# Aux_Power_Board.net
KiCad netlist of a schematic drawn in EAGLE
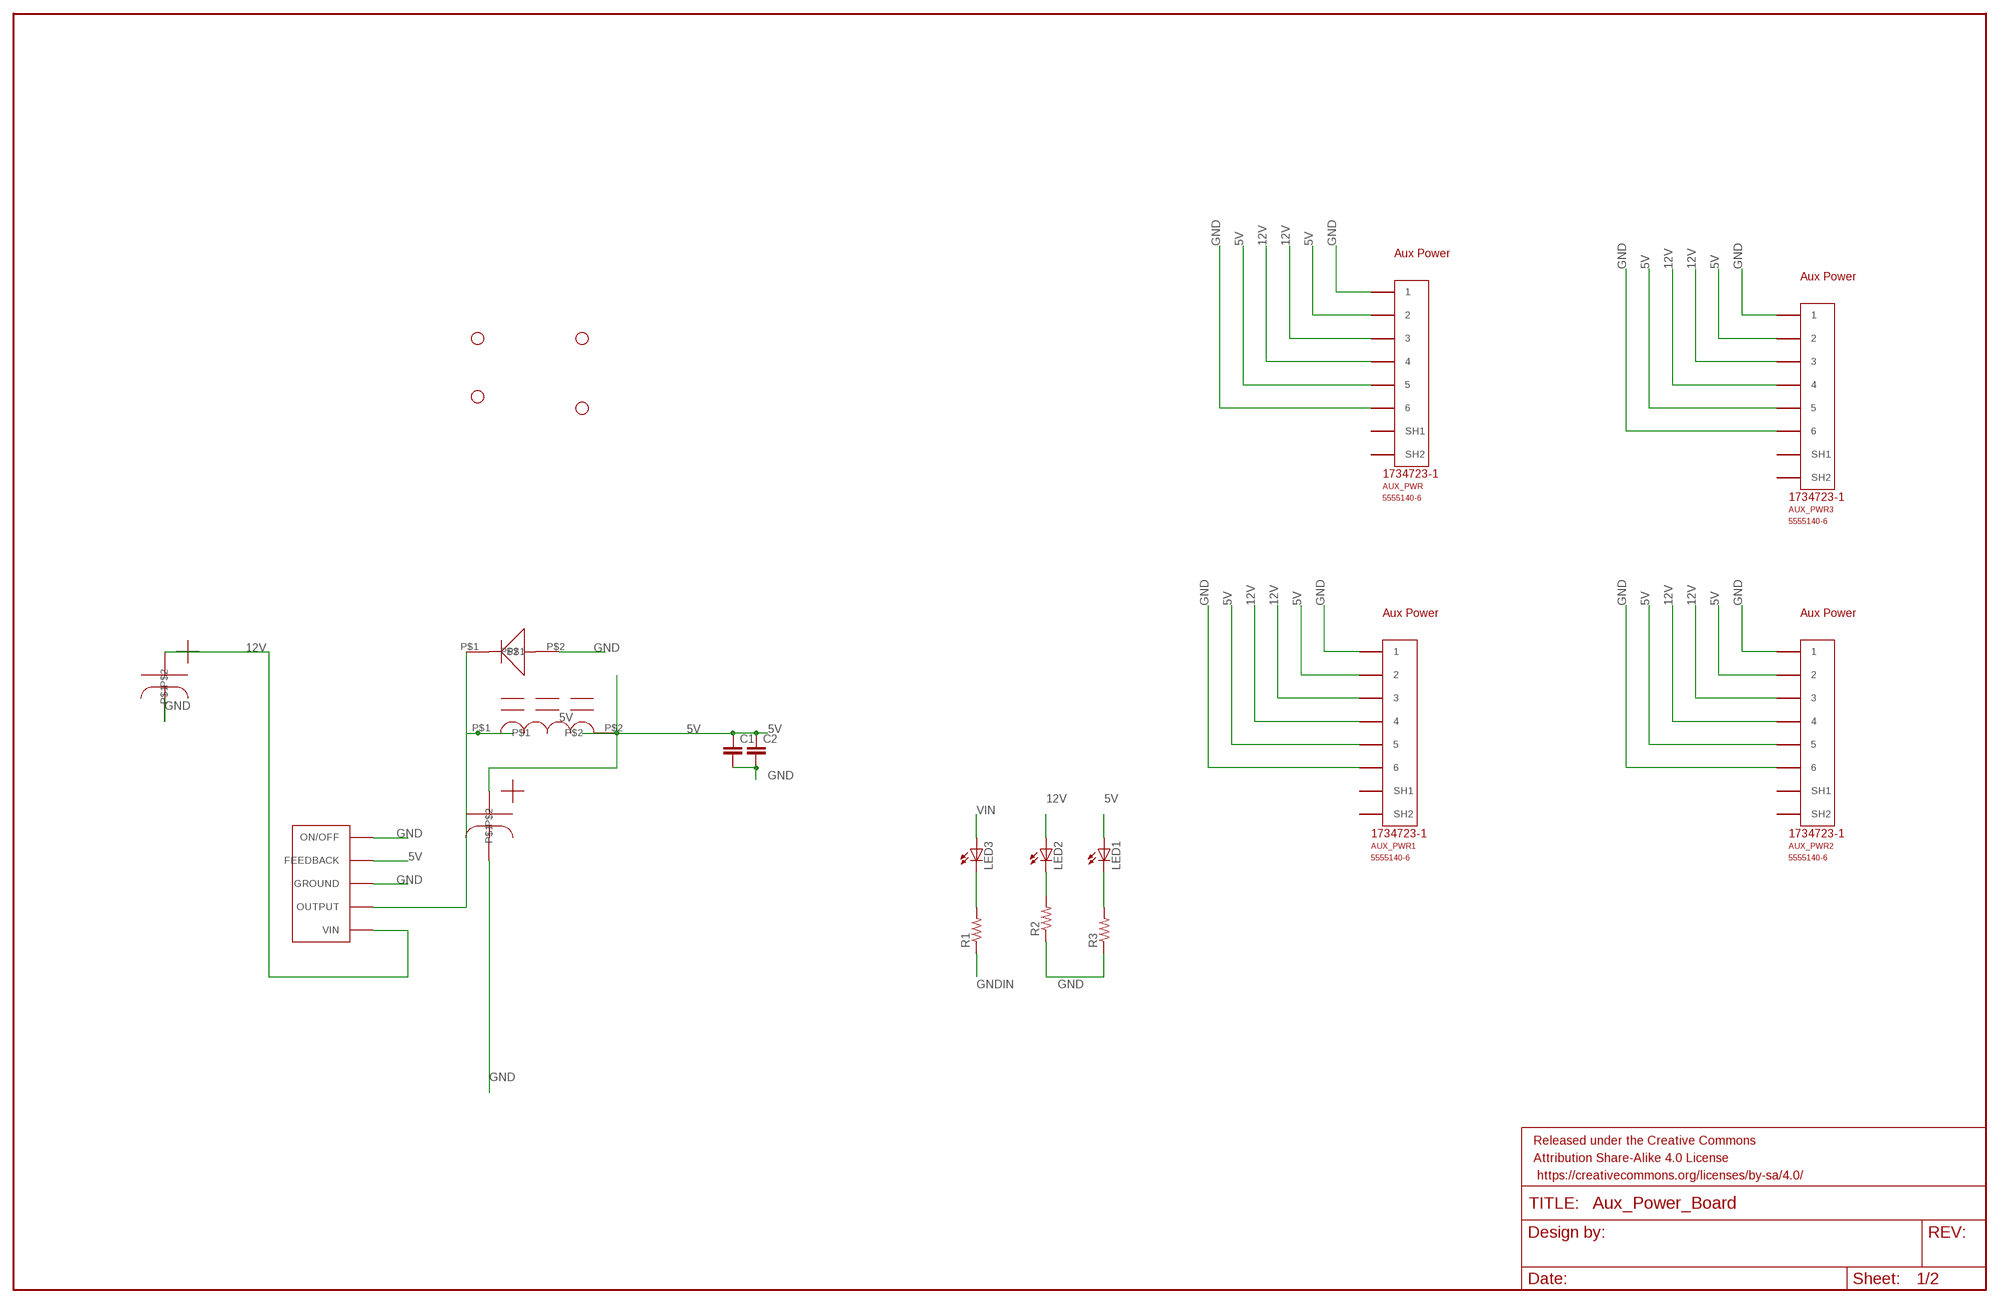
[diagram p0: schematic, sheet 1]
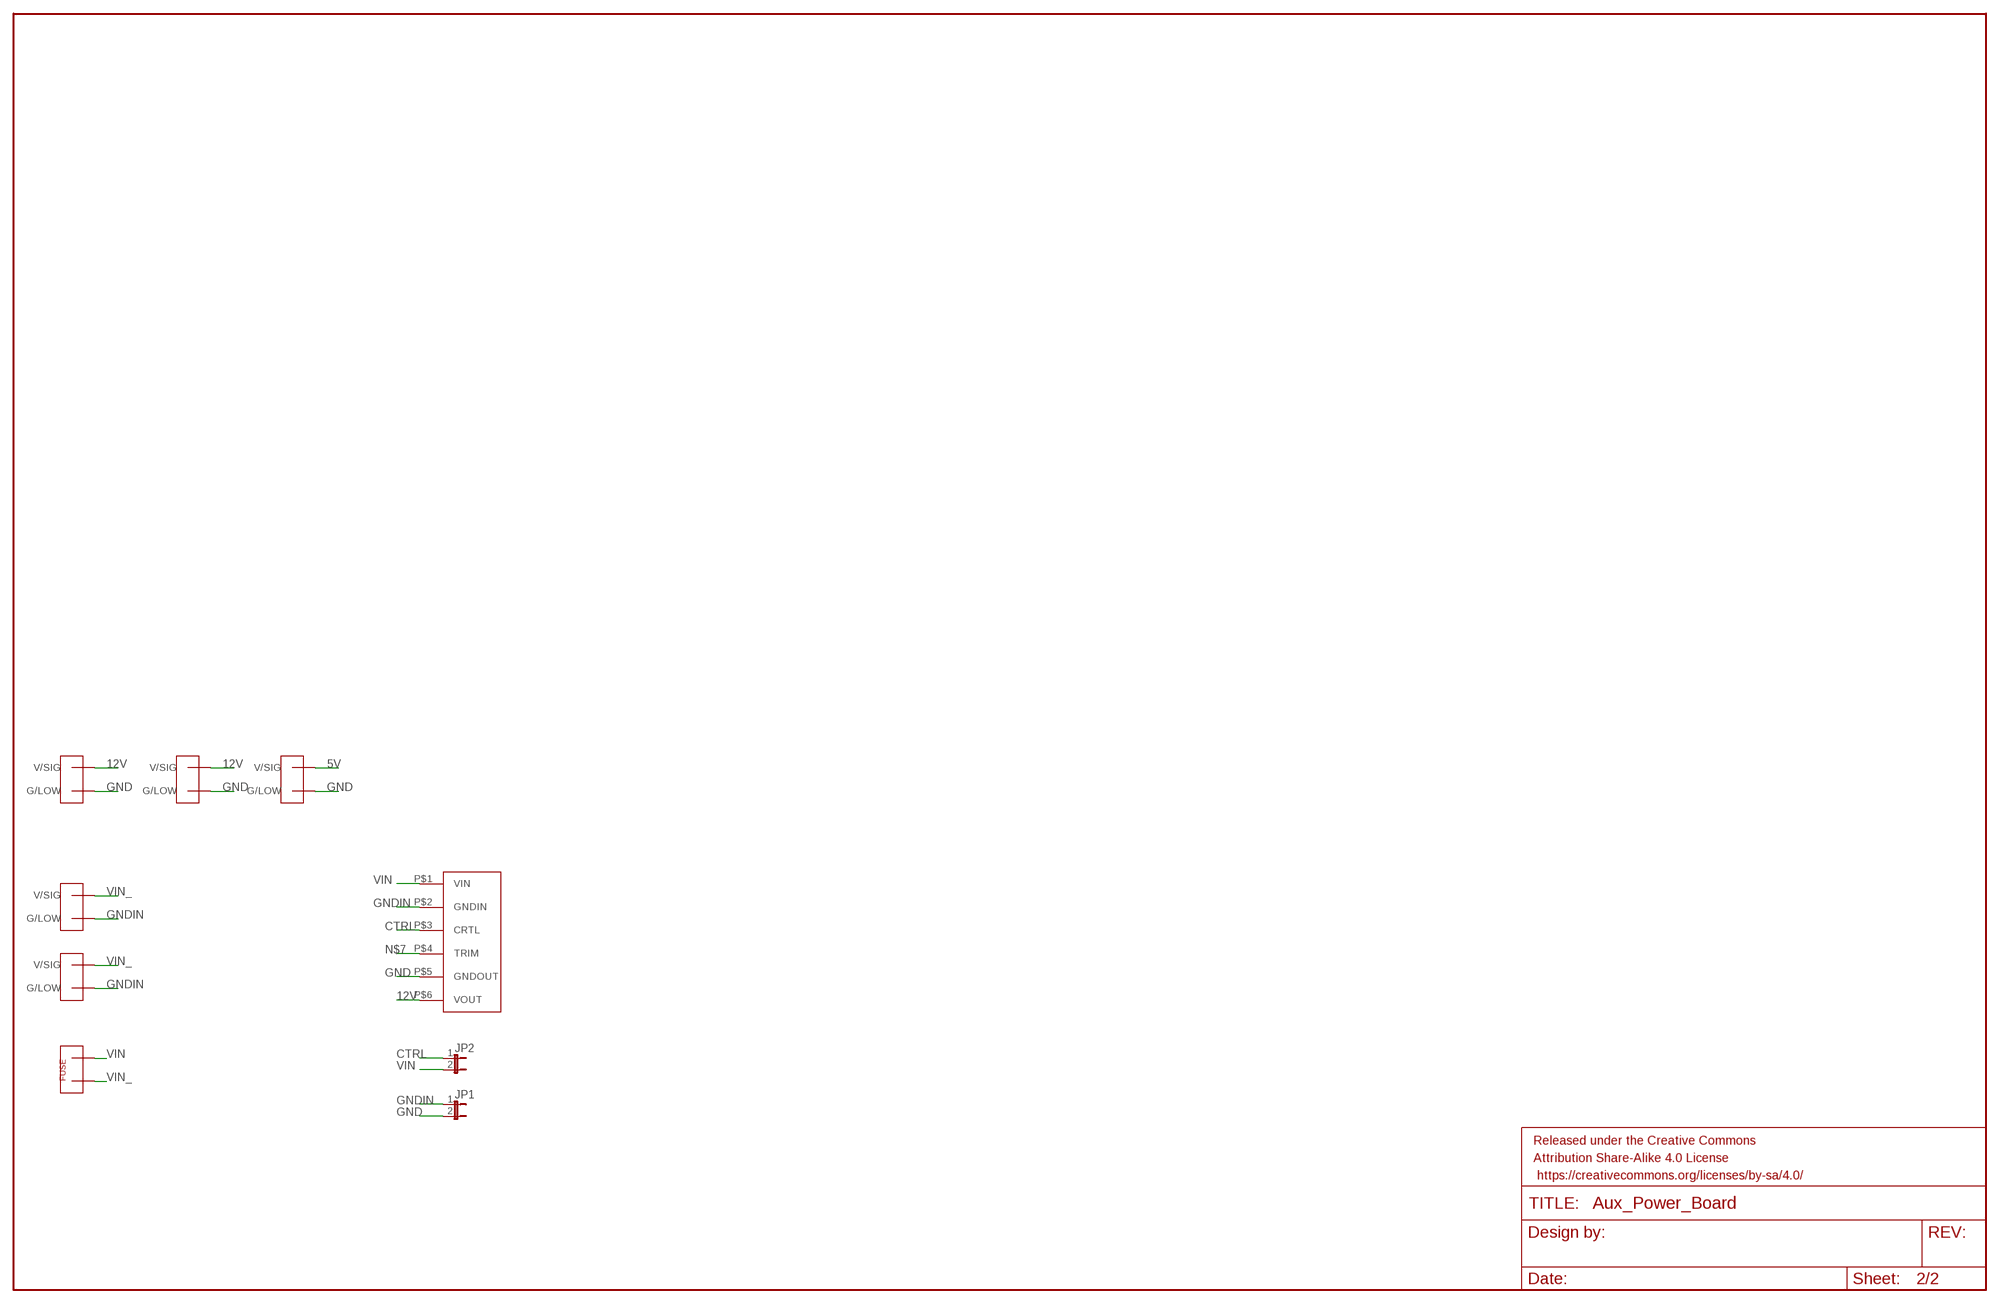
[diagram p1: schematic, sheet 2]

(export (version "E")
  (design (tool "Eeschema 10.0.6"))
  (components
    (comp (ref "FRAME2")
      (value "FRAME-LEDGER")
      (footprint "eagle-import:CREATIVE_COMMONS")
      (libsource (lib "eagle-import") (part "FRAME-LEDGER"))
    )
    (comp (ref "JP1")
      (value "JP1E")
      (footprint "eagle-import:JP1")
      (libsource (lib "eagle-import") (part "JP1E"))
    )
    (comp (ref "JP2")
      (value "JP1E")
      (footprint "eagle-import:JP1")
      (libsource (lib "eagle-import") (part "JP1E"))
    )
    (comp (ref "U$1")
      (value "TE770966")
      (footprint "eagle-import:2X1-MATE-N-LOCK")
      (libsource (lib "eagle-import") (part "TE770966"))
    )
    (comp (ref "U$2")
      (value "TE770966")
      (footprint "eagle-import:2X1-MATE-N-LOCK")
      (libsource (lib "eagle-import") (part "TE770966"))
    )
    (comp (ref "U$3")
      (value "TE770966")
      (footprint "eagle-import:2X1-MATE-N-LOCK")
      (libsource (lib "eagle-import") (part "TE770966"))
    )
    (comp (ref "U$12")
      (value "RPA60-2412SFW_P")
      (footprint "eagle-import:RPA60-2412SFW_P")
      (libsource (lib "eagle-import") (part "RPA60-2412SFW_P"))
    )
    (comp (ref "U$13")
      (value "FUSEMINI-BLADE")
      (footprint "eagle-import:MINI-BLADE-FUSE")
      (libsource (lib "eagle-import") (part "FUSEMINI-BLADE"))
    )
    (comp (ref "U$14")
      (value "TE770966")
      (footprint "eagle-import:2X1-MATE-N-LOCK")
      (libsource (lib "eagle-import") (part "TE770966"))
    )
    (comp (ref "U$15")
      (value "TE770966")
      (footprint "eagle-import:2X1-MATE-N-LOCK")
      (libsource (lib "eagle-import") (part "TE770966"))
    )
    (comp (ref "AUX_PWR")
      (value "5555140-6")
      (footprint "eagle-import:1734723-1_RJ11")
      (libsource (lib "eagle-import") (part "5555140-6"))
    )
    (comp (ref "AUX_PWR1")
      (value "5555140-6")
      (footprint "eagle-import:1734723-1_RJ11")
      (libsource (lib "eagle-import") (part "5555140-6"))
    )
    (comp (ref "AUX_PWR2")
      (value "5555140-6")
      (footprint "eagle-import:1734723-1_RJ11")
      (libsource (lib "eagle-import") (part "5555140-6"))
    )
    (comp (ref "AUX_PWR3")
      (value "5555140-6")
      (footprint "eagle-import:1734723-1_RJ11")
      (libsource (lib "eagle-import") (part "5555140-6"))
    )
    (comp (ref "C1")
      (value "CAP0805")
      (footprint "eagle-import:0805")
      (libsource (lib "eagle-import") (part "CAP0805"))
    )
    (comp (ref "C2")
      (value "CAP0805")
      (footprint "eagle-import:0805")
      (libsource (lib "eagle-import") (part "CAP0805"))
    )
    (comp (ref "FRAME1")
      (value "FRAME-LEDGER")
      (footprint "eagle-import:CREATIVE_COMMONS")
      (libsource (lib "eagle-import") (part "FRAME-LEDGER"))
    )
    (comp (ref "H1")
      (value "STAND-OFF")
      (footprint "eagle-import:STAND-OFF")
      (libsource (lib "eagle-import") (part "STAND-OFF"))
    )
    (comp (ref "H2")
      (value "STAND-OFF")
      (footprint "eagle-import:STAND-OFF")
      (libsource (lib "eagle-import") (part "STAND-OFF"))
    )
    (comp (ref "H3")
      (value "STAND-OFF")
      (footprint "eagle-import:STAND-OFF")
      (libsource (lib "eagle-import") (part "STAND-OFF"))
    )
    (comp (ref "H4")
      (value "STAND-OFF")
      (footprint "eagle-import:STAND-OFF")
      (libsource (lib "eagle-import") (part "STAND-OFF"))
    )
    (comp (ref "LED1")
      (value "LEDCHIP-LED0805")
      (footprint "eagle-import:CHIP-LED0805")
      (libsource (lib "eagle-import") (part "LEDCHIP-LED0805"))
    )
    (comp (ref "LED2")
      (value "LEDCHIP-LED0805")
      (footprint "eagle-import:CHIP-LED0805")
      (libsource (lib "eagle-import") (part "LEDCHIP-LED0805"))
    )
    (comp (ref "LED3")
      (value "LEDCHIP-LED0805")
      (footprint "eagle-import:CHIP-LED0805")
      (libsource (lib "eagle-import") (part "LEDCHIP-LED0805"))
    )
    (comp (ref "R1")
      (value "R-US_M0805")
      (footprint "eagle-import:M0805")
      (libsource (lib "eagle-import") (part "R-US_M0805"))
    )
    (comp (ref "R2")
      (value "R-US_M0805")
      (footprint "eagle-import:M0805")
      (libsource (lib "eagle-import") (part "R-US_M0805"))
    )
    (comp (ref "R3")
      (value "R-US_M0805")
      (footprint "eagle-import:M0805")
      (libsource (lib "eagle-import") (part "R-US_M0805"))
    )
    (comp (ref "U$4")
      (value "MBR360GOS")
      (footprint "eagle-import:MBR360GOS")
      (libsource (lib "eagle-import") (part "MBR360GOS"))
    )
    (comp (ref "U$7")
      (value "LM2576")
      (footprint "eagle-import:D2PAK-5")
      (libsource (lib "eagle-import") (part "LM2576"))
    )
    (comp (ref "U$8")
      (value "CAPESK107M025AC3AA")
      (footprint "eagle-import:ESK107M025AC3AA")
      (libsource (lib "eagle-import") (part "CAPESK107M025AC3AA"))
    )
    (comp (ref "U$9")
      (value "CAPESK108M025AH4EA")
      (footprint "eagle-import:ESK108M025AH4EA")
      (libsource (lib "eagle-import") (part "CAPESK108M025AH4EA"))
    )
    (comp (ref "U$10")
      (value "M1418-ND")
      (footprint "eagle-import:M1418-ND")
      (libsource (lib "eagle-import") (part "M1418-ND"))
    )
  )
  (nets
    (net (code "1") (name "5V") (class "Default")
      (node (ref "AUX_PWR") (pin "2") (pinfunction "2_2") (pintype "bidirectional"))
      (node (ref "AUX_PWR") (pin "5") (pinfunction "5_5") (pintype "bidirectional"))
      (node (ref "AUX_PWR1") (pin "2") (pinfunction "2_2") (pintype "bidirectional"))
      (node (ref "AUX_PWR1") (pin "5") (pinfunction "5_5") (pintype "bidirectional"))
      (node (ref "AUX_PWR2") (pin "2") (pinfunction "2_2") (pintype "bidirectional"))
      (node (ref "AUX_PWR2") (pin "5") (pinfunction "5_5") (pintype "bidirectional"))
      (node (ref "AUX_PWR3") (pin "2") (pinfunction "2_2") (pintype "bidirectional"))
      (node (ref "AUX_PWR3") (pin "5") (pinfunction "5_5") (pintype "bidirectional"))
      (node (ref "C1") (pin "1") (pinfunction "1_1") (pintype "passive"))
      (node (ref "C2") (pin "1") (pinfunction "1_1") (pintype "passive"))
      (node (ref "LED1") (pin "A") (pinfunction "A_A") (pintype "passive"))
      (node (ref "U$10") (pin "P$2") (pinfunction "P$2_P$2") (pintype "bidirectional"))
      (node (ref "U$3") (pin "CIRCUIT1") (pinfunction "V/SIG_CIRCUIT1") (pintype "bidirectional"))
      (node (ref "U$7") (pin "4") (pinfunction "FEEDBACK_4") (pintype "bidirectional"))
      (node (ref "U$9") (pin "P$1") (pinfunction "P$1_P$1") (pintype "bidirectional"))
    )
    (net (code "2") (name "12V") (class "Default")
      (node (ref "AUX_PWR") (pin "3") (pinfunction "3_3") (pintype "bidirectional"))
      (node (ref "AUX_PWR") (pin "4") (pinfunction "4_4") (pintype "bidirectional"))
      (node (ref "AUX_PWR1") (pin "3") (pinfunction "3_3") (pintype "bidirectional"))
      (node (ref "AUX_PWR1") (pin "4") (pinfunction "4_4") (pintype "bidirectional"))
      (node (ref "AUX_PWR2") (pin "3") (pinfunction "3_3") (pintype "bidirectional"))
      (node (ref "AUX_PWR2") (pin "4") (pinfunction "4_4") (pintype "bidirectional"))
      (node (ref "AUX_PWR3") (pin "3") (pinfunction "3_3") (pintype "bidirectional"))
      (node (ref "AUX_PWR3") (pin "4") (pinfunction "4_4") (pintype "bidirectional"))
      (node (ref "LED2") (pin "A") (pinfunction "A_A") (pintype "passive"))
      (node (ref "U$1") (pin "CIRCUIT1") (pinfunction "V/SIG_CIRCUIT1") (pintype "bidirectional"))
      (node (ref "U$12") (pin "P$6") (pinfunction "VOUT_P$6") (pintype "bidirectional"))
      (node (ref "U$2") (pin "CIRCUIT1") (pinfunction "V/SIG_CIRCUIT1") (pintype "bidirectional"))
      (node (ref "U$7") (pin "1") (pinfunction "VIN_1") (pintype "bidirectional"))
      (node (ref "U$8") (pin "P$1") (pinfunction "P$1_P$1") (pintype "bidirectional"))
    )
    (net (code "3") (name "CTRL") (class "Default")
      (node (ref "JP2") (pin "1") (pinfunction "1_1") (pintype "passive"))
      (node (ref "U$12") (pin "P$3") (pinfunction "CRTL_P$3") (pintype "bidirectional"))
    )
    (net (code "4") (name "GND") (class "Default")
      (node (ref "AUX_PWR") (pin "1") (pinfunction "1_1") (pintype "bidirectional"))
      (node (ref "AUX_PWR") (pin "6") (pinfunction "6_6") (pintype "bidirectional"))
      (node (ref "AUX_PWR1") (pin "1") (pinfunction "1_1") (pintype "bidirectional"))
      (node (ref "AUX_PWR1") (pin "6") (pinfunction "6_6") (pintype "bidirectional"))
      (node (ref "AUX_PWR2") (pin "1") (pinfunction "1_1") (pintype "bidirectional"))
      (node (ref "AUX_PWR2") (pin "6") (pinfunction "6_6") (pintype "bidirectional"))
      (node (ref "AUX_PWR3") (pin "1") (pinfunction "1_1") (pintype "bidirectional"))
      (node (ref "AUX_PWR3") (pin "6") (pinfunction "6_6") (pintype "bidirectional"))
      (node (ref "C1") (pin "2") (pinfunction "2_2") (pintype "passive"))
      (node (ref "C2") (pin "2") (pinfunction "2_2") (pintype "passive"))
      (node (ref "JP1") (pin "2") (pinfunction "2_2") (pintype "passive"))
      (node (ref "R2") (pin "1") (pinfunction "1_1") (pintype "passive"))
      (node (ref "R3") (pin "1") (pinfunction "1_1") (pintype "passive"))
      (node (ref "U$1") (pin "CIRCUIT2") (pinfunction "G/LOW_CIRCUIT2") (pintype "bidirectional"))
      (node (ref "U$12") (pin "P$5") (pinfunction "GNDOUT_P$5") (pintype "bidirectional"))
      (node (ref "U$2") (pin "CIRCUIT2") (pinfunction "G/LOW_CIRCUIT2") (pintype "bidirectional"))
      (node (ref "U$3") (pin "CIRCUIT2") (pinfunction "G/LOW_CIRCUIT2") (pintype "bidirectional"))
      (node (ref "U$4") (pin "P$2") (pinfunction "P$1_P$2") (pintype "bidirectional"))
      (node (ref "U$7") (pin "3") (pinfunction "GROUND_3") (pintype "bidirectional"))
      (node (ref "U$7") (pin "5") (pinfunction "ON/OFF_5") (pintype "bidirectional"))
      (node (ref "U$7") (pin "GROUND") (pinfunction "GROUND_GROUND") (pintype "bidirectional"))
      (node (ref "U$8") (pin "P$2") (pinfunction "P$2_P$2") (pintype "bidirectional"))
      (node (ref "U$9") (pin "P$2") (pinfunction "P$2_P$2") (pintype "bidirectional"))
    )
    (net (code "5") (name "GNDIN") (class "Default")
      (node (ref "JP1") (pin "1") (pinfunction "1_1") (pintype "passive"))
      (node (ref "R1") (pin "1") (pinfunction "1_1") (pintype "passive"))
      (node (ref "U$12") (pin "P$2") (pinfunction "GNDIN_P$2") (pintype "bidirectional"))
      (node (ref "U$14") (pin "CIRCUIT2") (pinfunction "G/LOW_CIRCUIT2") (pintype "bidirectional"))
      (node (ref "U$15") (pin "CIRCUIT2") (pinfunction "G/LOW_CIRCUIT2") (pintype "bidirectional"))
    )
    (net (code "6") (name "N$7") (class "Default")
      (node (ref "U$12") (pin "P$4") (pinfunction "TRIM_P$4") (pintype "bidirectional"))
    )
    (net (code "7") (name "Net-(LED1-PadC)") (class "Default")
      (node (ref "LED1") (pin "C") (pinfunction "C_C") (pintype "passive"))
      (node (ref "R3") (pin "2") (pinfunction "2_2") (pintype "passive"))
    )
    (net (code "8") (name "Net-(LED2-PadC)") (class "Default")
      (node (ref "LED2") (pin "C") (pinfunction "C_C") (pintype "passive"))
      (node (ref "R2") (pin "2") (pinfunction "2_2") (pintype "passive"))
    )
    (net (code "9") (name "Net-(LED3-PadC)") (class "Default")
      (node (ref "LED3") (pin "C") (pinfunction "C_C") (pintype "passive"))
      (node (ref "R1") (pin "2") (pinfunction "2_2") (pintype "passive"))
    )
    (net (code "10") (name "Net-(U$4-P$2)") (class "Default")
      (node (ref "U$10") (pin "P$1") (pinfunction "P$1_P$1") (pintype "bidirectional"))
      (node (ref "U$4") (pin "P$1") (pinfunction "P$2_P$1") (pintype "bidirectional"))
      (node (ref "U$7") (pin "2") (pinfunction "OUTPUT_2") (pintype "bidirectional"))
    )
    (net (code "11") (name "VIN") (class "Default")
      (node (ref "JP2") (pin "2") (pinfunction "2_2") (pintype "passive"))
      (node (ref "LED3") (pin "A") (pinfunction "A_A") (pintype "passive"))
      (node (ref "U$12") (pin "P$1") (pinfunction "VIN_P$1") (pintype "bidirectional"))
      (node (ref "U$13") (pin "OUT") (pinfunction "OUT_OUT") (pintype "bidirectional"))
    )
    (net (code "12") (name "VIN_") (class "Default")
      (node (ref "U$13") (pin "IN") (pinfunction "IN_IN") (pintype "bidirectional"))
      (node (ref "U$14") (pin "CIRCUIT1") (pinfunction "V/SIG_CIRCUIT1") (pintype "bidirectional"))
      (node (ref "U$15") (pin "CIRCUIT1") (pinfunction "V/SIG_CIRCUIT1") (pintype "bidirectional"))
    )
    (net (code "13") (name "unconnected-(AUX_PWR-PadSH1)") (class "Default")
      (node (ref "AUX_PWR") (pin "SH1") (pinfunction "SH1_SH1") (pintype "bidirectional"))
    )
    (net (code "14") (name "unconnected-(AUX_PWR-PadSH2)") (class "Default")
      (node (ref "AUX_PWR") (pin "SH2") (pinfunction "SH2_SH2") (pintype "bidirectional"))
    )
    (net (code "15") (name "unconnected-(AUX_PWR1-PadSH1)") (class "Default")
      (node (ref "AUX_PWR1") (pin "SH1") (pinfunction "SH1_SH1") (pintype "bidirectional"))
    )
    (net (code "16") (name "unconnected-(AUX_PWR1-PadSH2)") (class "Default")
      (node (ref "AUX_PWR1") (pin "SH2") (pinfunction "SH2_SH2") (pintype "bidirectional"))
    )
    (net (code "17") (name "unconnected-(AUX_PWR2-PadSH1)") (class "Default")
      (node (ref "AUX_PWR2") (pin "SH1") (pinfunction "SH1_SH1") (pintype "bidirectional"))
    )
    (net (code "18") (name "unconnected-(AUX_PWR2-PadSH2)") (class "Default")
      (node (ref "AUX_PWR2") (pin "SH2") (pinfunction "SH2_SH2") (pintype "bidirectional"))
    )
    (net (code "19") (name "unconnected-(AUX_PWR3-PadSH1)") (class "Default")
      (node (ref "AUX_PWR3") (pin "SH1") (pinfunction "SH1_SH1") (pintype "bidirectional"))
    )
    (net (code "20") (name "unconnected-(AUX_PWR3-PadSH2)") (class "Default")
      (node (ref "AUX_PWR3") (pin "SH2") (pinfunction "SH2_SH2") (pintype "bidirectional"))
    )
  )
)
